# REF_VOLTAGE_RELAY_DRIVER.net
KiCad netlist of a schematic drawn in Altium Designer
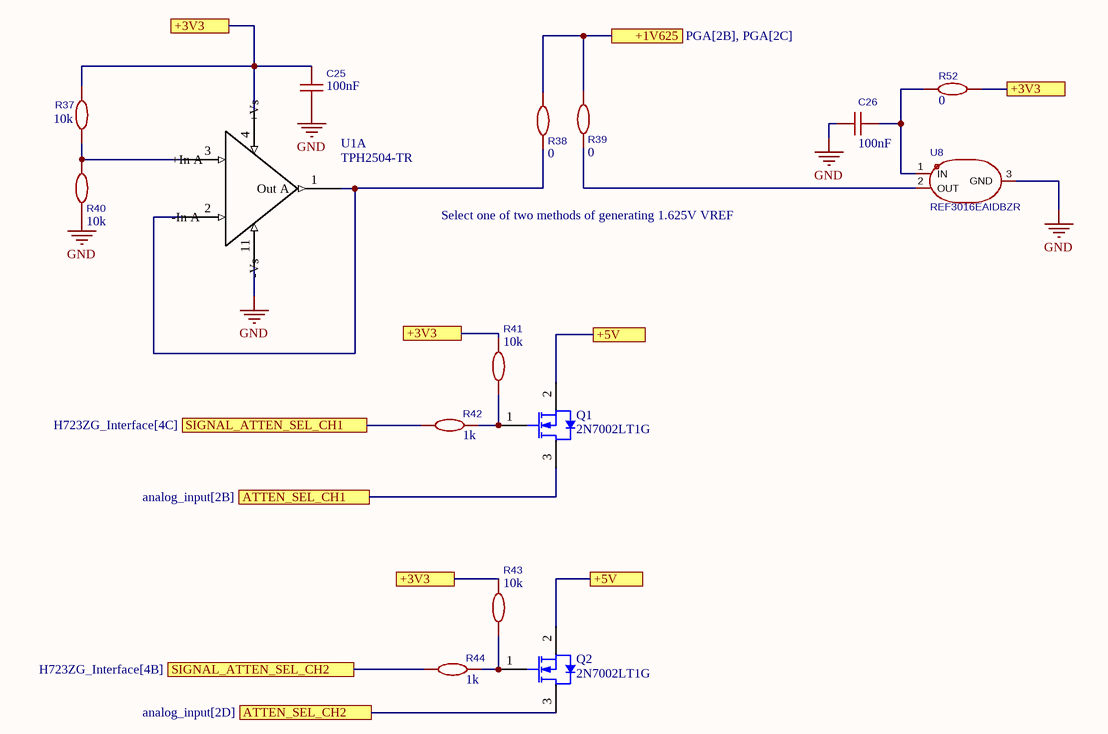
[diagram p0: REF_VOLTAGE_RELAY_DRIVER.SchDoc]

(export (version "E")
  (design (tool "Eeschema 10.0.6"))
  (components
    (comp (ref "C25")
      (value "100nF")
      (footprint "C0805")
      (description "Capacitance:100nF Tolerance:±5% Tolerance:±5% Voltage Rating:50V Temperature Coefficient:X7R")
      (fields (field (name "MANUFACTURER") "YAGEO(国巨)") (field (name "TOLERANCE") "5%"))
      (libsource (lib "zhiming xue") (part "0805CG6R0C500NT_C67560"))
    )
    (comp (ref "C26")
      (value "100nF")
      (footprint "C0805")
      (description "Capacitance:100nF Tolerance:±5% Tolerance:±5% Voltage Rating:50V Temperature Coefficient:X7R")
      (fields (field (name "MANUFACTURER") "YAGEO(国巨)") (field (name "TOLERANCE") "5%"))
      (libsource (lib "zhiming xue") (part "0805CG6R0C500NT_C67560"))
    )
    (comp (ref "Q1")
      (value "2N7002LT1G")
      (footprint "ONSC-SOT-23-3-318-08_V")
      (description "Small Signal MOSFET, 60 V, 115 mA, N-Channel, 3-Pin SOT-23, Pb-Free, Tape and Reel")
      (fields (field (name "MANUFACTURER") "On Semiconductor"))
      (libsource (lib "Altium Content Vault") (part "ONSC-NMOS-G1S2D3-3"))
    )
    (comp (ref "Q2")
      (value "2N7002LT1G")
      (footprint "ONSC-SOT-23-3-318-08_V")
      (description "Small Signal MOSFET, 60 V, 115 mA, N-Channel, 3-Pin SOT-23, Pb-Free, Tape and Reel")
      (fields (field (name "MANUFACTURER") "On Semiconductor"))
      (libsource (lib "Altium Content Vault") (part "ONSC-NMOS-G1S2D3-3"))
    )
    (comp (ref "R37")
      (value "10k")
      (footprint "R0805")
      (fields
        (field (name "MANUFACTURER") "UNI-ROYAL(厚声)")
        (field (name "TOLERANCE") "1%")
        (field (name "MANUFACTURER PART NUMBER") "0805W8F1002T5E")
      )
      (libsource (lib "zhiming xue") (part "0805W8F0000T5E_C17477"))
    )
    (comp (ref "R38")
      (value "0")
      (footprint "R0805")
      (fields
        (field (name "MANUFACTURER") "UNI-ROYAL(厚声)")
        (field (name "TOLERANCE") "1%")
        (field (name "MANUFACTURER PART NUMBER") "0805W8F0000T5E")
      )
      (libsource (lib "zhiming xue") (part "0805W8F0000T5E_C17477"))
    )
    (comp (ref "R39")
      (value "0")
      (footprint "R0805")
      (fields
        (field (name "MANUFACTURER") "UNI-ROYAL(厚声)")
        (field (name "TOLERANCE") "1%")
        (field (name "MANUFACTURER PART NUMBER") "0805W8F0000T5E")
      )
      (libsource (lib "zhiming xue") (part "0805W8F0000T5E_C17477"))
    )
    (comp (ref "R40")
      (value "10k")
      (footprint "R0805")
      (fields
        (field (name "MANUFACTURER") "UNI-ROYAL(厚声)")
        (field (name "TOLERANCE") "1%")
        (field (name "MANUFACTURER PART NUMBER") "0805W8F1002T5E")
      )
      (libsource (lib "zhiming xue") (part "0805W8F0000T5E_C17477"))
    )
    (comp (ref "R41")
      (value "10k")
      (footprint "R0805")
      (fields
        (field (name "MANUFACTURER") "UNI-ROYAL(厚声)")
        (field (name "TOLERANCE") "1%")
        (field (name "MANUFACTURER PART NUMBER") "0805W8F1002T5E")
      )
      (libsource (lib "zhiming xue") (part "0805W8F0000T5E_C17477"))
    )
    (comp (ref "R42")
      (value "1k")
      (footprint "R0805")
      (fields
        (field (name "MANUFACTURER") "UNI-ROYAL(厚声)")
        (field (name "TOLERANCE") "1%")
        (field (name "MANUFACTURER PART NUMBER") "0805W8F1001T5E")
      )
      (libsource (lib "zhiming xue") (part "0805W8F0000T5E_C17477"))
    )
    (comp (ref "R43")
      (value "10k")
      (footprint "R0805")
      (fields
        (field (name "MANUFACTURER") "UNI-ROYAL(厚声)")
        (field (name "TOLERANCE") "1%")
        (field (name "MANUFACTURER PART NUMBER") "0805W8F1002T5E")
      )
      (libsource (lib "zhiming xue") (part "0805W8F0000T5E_C17477"))
    )
    (comp (ref "R44")
      (value "1k")
      (footprint "R0805")
      (fields
        (field (name "MANUFACTURER") "UNI-ROYAL(厚声)")
        (field (name "TOLERANCE") "1%")
        (field (name "MANUFACTURER PART NUMBER") "0805W8F1001T5E")
      )
      (libsource (lib "zhiming xue") (part "0805W8F0000T5E_C17477"))
    )
    (comp (ref "R52")
      (value "0")
      (footprint "R0805")
      (fields
        (field (name "MANUFACTURER") "UNI-ROYAL(厚声)")
        (field (name "TOLERANCE") "1%")
        (field (name "MANUFACTURER PART NUMBER") "0805W8F0000T5E")
      )
      (libsource (lib "zhiming xue") (part "0805W8F0000T5E_C17477"))
    )
    (comp (ref "U1")
      (value "TPH2504-TR")
      (footprint "TSOP65P640X120-14N")
      (description "Operational Amplifier, 4 Func, 5000uV Offset-Max, CMOS, PDSO14")
      (libsource (lib "zhiming xue") (part "TPH2504-TR-Symbol-1"))
    )
    (comp (ref "U8")
      (value "REF3016EAIDBZR")
      (footprint "SOT-23-3_L3.0-W1.7-P0.95-LS2.9-BR")
      (fields (field (name "MANUFACTURER") "TI(德州仪器)"))
      (libsource (lib "zhiming xue") (part "REF3016EAIDBZR"))
    )
  )
  (nets
    (net (code "1") (name "/+1V625") (class "Default")
      (node (ref "R38") (pin "1") (pinfunction "1_1") (pintype "passive"))
      (node (ref "R39") (pin "1") (pinfunction "1_1") (pintype "passive"))
    )
    (net (code "2") (name "/+3V3") (class "Default")
      (node (ref "C25") (pin "1") (pinfunction "1_1") (pintype "passive"))
      (node (ref "R37") (pin "1") (pinfunction "1_1") (pintype "passive"))
      (node (ref "R41") (pin "2") (pinfunction "2_2") (pintype "passive"))
      (node (ref "R43") (pin "2") (pinfunction "2_2") (pintype "passive"))
      (node (ref "R52") (pin "2") (pinfunction "2_2") (pintype "passive"))
      (node (ref "U1") (pin "4") (pinfunction "+Vs_4") (pintype "input"))
    )
    (net (code "3") (name "/+5V") (class "Default")
      (node (ref "Q1") (pin "2") (pinfunction "S_2") (pintype "passive"))
      (node (ref "Q2") (pin "2") (pinfunction "S_2") (pintype "passive"))
    )
    (net (code "5") (name "/ATTEN_SEL_CH1") (class "Default")
      (node (ref "Q1") (pin "3") (pinfunction "D_3") (pintype "passive"))
    )
    (net (code "6") (name "/ATTEN_SEL_CH2") (class "Default")
      (node (ref "Q2") (pin "3") (pinfunction "D_3") (pintype "passive"))
    )
    (net (code "7") (name "/SIGNAL_ATTEN_SEL_CH1") (class "Default")
      (node (ref "R42") (pin "1") (pinfunction "1_1") (pintype "passive"))
    )
    (net (code "8") (name "/SIGNAL_ATTEN_SEL_CH2") (class "Default")
      (node (ref "R44") (pin "1") (pinfunction "1_1") (pintype "passive"))
    )
    (net (code "9") (name "GND") (class "Default")
      (node (ref "C25") (pin "2") (pinfunction "2_2") (pintype "passive"))
      (node (ref "C26") (pin "1") (pinfunction "1_1") (pintype "passive"))
      (node (ref "R40") (pin "2") (pinfunction "2_2") (pintype "passive"))
      (node (ref "U1") (pin "11") (pinfunction "-Vs_11") (pintype "input"))
      (node (ref "U8") (pin "3") (pinfunction "GND_3") (pintype "passive"))
    )
    (net (code "10") (name "Net-(Q1-G)") (class "Default")
      (node (ref "Q1") (pin "1") (pinfunction "G_1") (pintype "passive"))
      (node (ref "R41") (pin "1") (pinfunction "1_1") (pintype "passive"))
      (node (ref "R42") (pin "2") (pinfunction "2_2") (pintype "passive"))
    )
    (net (code "11") (name "Net-(Q2-G)") (class "Default")
      (node (ref "Q2") (pin "1") (pinfunction "G_1") (pintype "passive"))
      (node (ref "R43") (pin "1") (pinfunction "1_1") (pintype "passive"))
      (node (ref "R44") (pin "2") (pinfunction "2_2") (pintype "passive"))
    )
    (net (code "12") (name "Net-(U1A-+In_A)") (class "Default")
      (node (ref "R37") (pin "2") (pinfunction "2_2") (pintype "passive"))
      (node (ref "R40") (pin "1") (pinfunction "1_1") (pintype "passive"))
      (node (ref "U1") (pin "3") (pinfunction "+In_A_3") (pintype "input"))
    )
    (net (code "13") (name "Net-(U1A--In_A)") (class "Default")
      (node (ref "R38") (pin "2") (pinfunction "2_2") (pintype "passive"))
      (node (ref "U1") (pin "1") (pinfunction "Out_A_1") (pintype "output"))
      (node (ref "U1") (pin "2") (pinfunction "-In_A_2") (pintype "input"))
    )
    (net (code "14") (name "Net-(U8-IN)") (class "Default")
      (node (ref "C26") (pin "2") (pinfunction "2_2") (pintype "passive"))
      (node (ref "R52") (pin "1") (pinfunction "1_1") (pintype "passive"))
      (node (ref "U8") (pin "1") (pinfunction "IN_1") (pintype "passive"))
    )
    (net (code "15") (name "Net-(U8-OUT)") (class "Default")
      (node (ref "R39") (pin "2") (pinfunction "2_2") (pintype "passive"))
      (node (ref "U8") (pin "2") (pinfunction "OUT_2") (pintype "passive"))
    )
  )
)
